# 205-020_001_smps_boost_fromCell.net
KiCad netlist of a schematic drawn in EAGLE
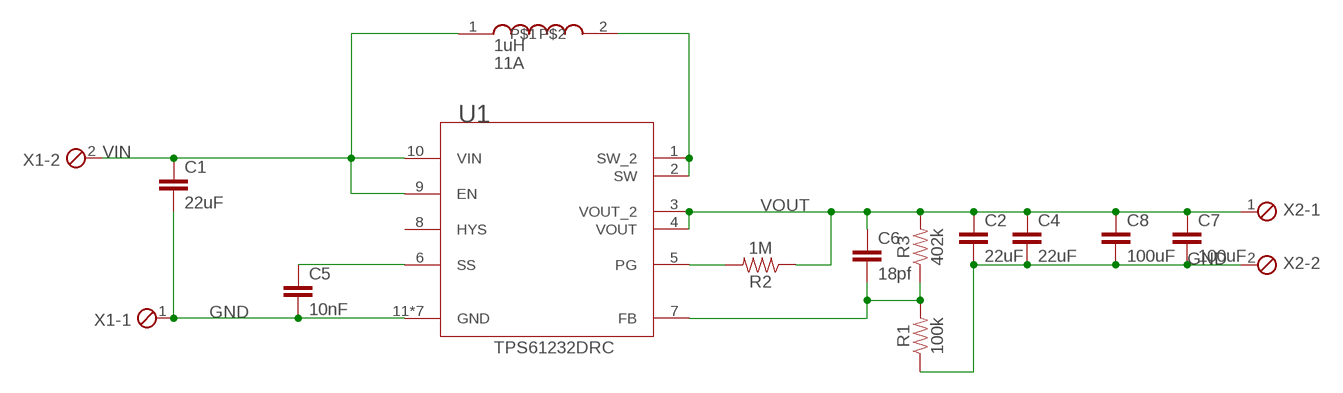
[diagram p0: schematic, sheet 1]

(export (version "E")
  (design (tool "Eeschema 10.0.6"))
  (components
    (comp (ref "C1")
      (value "22uF")
      (footprint "eagle-import:0805")
      (libsource (lib "eagle-import") (part "22UF-0805-16V-20%"))
    )
    (comp (ref "C2")
      (value "22uF")
      (footprint "eagle-import:0805")
      (libsource (lib "eagle-import") (part "22UF-0805-16V-20%"))
    )
    (comp (ref "C4")
      (value "22uF")
      (footprint "eagle-import:0805")
      (libsource (lib "eagle-import") (part "22UF-0805-16V-20%"))
    )
    (comp (ref "C5")
      (value "10nF")
      (footprint "eagle-import:0603")
      (libsource (lib "eagle-import") (part "10NF-0603-50V-10%"))
    )
    (comp (ref "C6")
      (value "18pf")
      (footprint "eagle-import:0805")
      (libsource (lib "eagle-import") (part "CAP-0805"))
    )
    (comp (ref "C7")
      (value "100uF")
      (footprint "eagle-import:1206")
      (libsource (lib "eagle-import") (part "CAP-1206"))
    )
    (comp (ref "C8")
      (value "100uF")
      (footprint "eagle-import:1206")
      (libsource (lib "eagle-import") (part "CAP-1206"))
    )
    (comp (ref "R1")
      (value "100k")
      (footprint "eagle-import:0603")
      (libsource (lib "eagle-import") (part "100KOHM-0603-1/10W-1%"))
    )
    (comp (ref "R2")
      (value "1M")
      (footprint "eagle-import:0603")
      (libsource (lib "eagle-import") (part "1MOHM-0603-1/4W-5%"))
    )
    (comp (ref "R3")
      (value "402k")
      (footprint "eagle-import:0603")
      (libsource (lib "eagle-import") (part "100KOHM-0603-1/10W-1%"))
    )
    (comp (ref "U$1")
      (value "1uH")
      (footprint "eagle-import:07A7")
      (fields (field (name "CURRENT") "11A") (field (name "INDUCTANCE") "1uH"))
      (libsource (lib "eagle-import") (part "LMLP0707"))
    )
    (comp (ref "U1")
      (value "TPS61232DRCR")
      (footprint "eagle-import:DRC0010G")
      (fields
        (field (name "MANUFACTURER") "Texas Instruments")
        (field (name "PARTNUMBER") "TPS61232DRC")
        (field (name "APPROVEDBY") "Not shown in title block")
        (field (name "AUTHOR") "Not shown in title block")
        (field (name "CHECKEDBY") "Not shown in title block")
        (field (name "ENGINEER") "Not shown in title block")
        (field (name "MODIFIEDDATE") "Not shown in title block")
        (field (name "PUBLISHER") "Texas Instruments")
        (field (name "SYMBOLCREATOR") "a0411947")
      )
      (libsource (lib "eagle-import") (part "TPS61232DRCR"))
    )
    (comp (ref "X1")
      (value "MPT2")
      (footprint "eagle-import:2POL254")
      (libsource (lib "eagle-import") (part "MPT2"))
    )
    (comp (ref "X2")
      (value "MPT2")
      (footprint "eagle-import:2POL254")
      (libsource (lib "eagle-import") (part "MPT2"))
    )
  )
  (nets
    (net (code "1") (name "/GND") (class "Default")
      (node (ref "C1") (pin "2") (pinfunction "2_2") (pintype "passive"))
      (node (ref "C2") (pin "2") (pinfunction "2_2") (pintype "passive"))
      (node (ref "C4") (pin "2") (pinfunction "2_2") (pintype "passive"))
      (node (ref "C5") (pin "2") (pinfunction "2_2") (pintype "passive"))
      (node (ref "C7") (pin "2") (pinfunction "2_2") (pintype "passive"))
      (node (ref "C8") (pin "2") (pinfunction "2_2") (pintype "passive"))
      (node (ref "R1") (pin "1") (pinfunction "1_1") (pintype "passive"))
      (node (ref "U1") (pin "11") (pinfunction "GND_11") (pintype "power_in"))
      (node (ref "U1") (pin "11A") (pinfunction "GND_11A") (pintype "power_in"))
      (node (ref "U1") (pin "11B") (pinfunction "GND_11B") (pintype "power_in"))
      (node (ref "U1") (pin "11C") (pinfunction "GND_11C") (pintype "power_in"))
      (node (ref "U1") (pin "11D") (pinfunction "GND_11D") (pintype "power_in"))
      (node (ref "U1") (pin "11E") (pinfunction "GND_11E") (pintype "power_in"))
      (node (ref "U1") (pin "11F") (pinfunction "GND_11F") (pintype "power_in"))
      (node (ref "X1") (pin "1") (pinfunction "1_1") (pintype "passive"))
      (node (ref "X2") (pin "2") (pinfunction "1_2") (pintype "passive"))
    )
    (net (code "2") (name "/VIN") (class "Default")
      (node (ref "C1") (pin "1") (pinfunction "1_1") (pintype "passive"))
      (node (ref "U$1") (pin "1") (pinfunction "P$1_1") (pintype "bidirectional"))
      (node (ref "U1") (pin "10") (pinfunction "VIN_10") (pintype "power_in"))
      (node (ref "U1") (pin "9") (pinfunction "EN_9") (pintype "input"))
      (node (ref "X1") (pin "2") (pinfunction "1_2") (pintype "passive"))
    )
    (net (code "3") (name "/VOUT") (class "Default")
      (node (ref "C2") (pin "1") (pinfunction "1_1") (pintype "passive"))
      (node (ref "C4") (pin "1") (pinfunction "1_1") (pintype "passive"))
      (node (ref "C6") (pin "1") (pinfunction "1_1") (pintype "passive"))
      (node (ref "C7") (pin "1") (pinfunction "1_1") (pintype "passive"))
      (node (ref "C8") (pin "1") (pinfunction "1_1") (pintype "passive"))
      (node (ref "R2") (pin "1") (pinfunction "1_1") (pintype "passive"))
      (node (ref "R3") (pin "2") (pinfunction "2_2") (pintype "passive"))
      (node (ref "U1") (pin "3") (pinfunction "VOUT_2_3") (pintype "power_in"))
      (node (ref "U1") (pin "4") (pinfunction "VOUT_4") (pintype "power_in"))
      (node (ref "X2") (pin "1") (pinfunction "1_1") (pintype "passive"))
    )
    (net (code "4") (name "Net-(U$1-P$2)") (class "Default")
      (node (ref "U$1") (pin "2") (pinfunction "P$2_2") (pintype "bidirectional"))
      (node (ref "U1") (pin "1") (pinfunction "SW_2_1") (pintype "power_in"))
      (node (ref "U1") (pin "2") (pinfunction "SW_2") (pintype "power_in"))
    )
    (net (code "5") (name "Net-(U1-FB)") (class "Default")
      (node (ref "C6") (pin "2") (pinfunction "2_2") (pintype "passive"))
      (node (ref "R1") (pin "2") (pinfunction "2_2") (pintype "passive"))
      (node (ref "R3") (pin "1") (pinfunction "1_1") (pintype "passive"))
      (node (ref "U1") (pin "7") (pinfunction "FB_7") (pintype "input"))
    )
    (net (code "6") (name "Net-(U1-PG)") (class "Default")
      (node (ref "R2") (pin "2") (pinfunction "2_2") (pintype "passive"))
      (node (ref "U1") (pin "5") (pinfunction "PG_5") (pintype "output"))
    )
    (net (code "7") (name "Net-(U1-SS)") (class "Default")
      (node (ref "C5") (pin "1") (pinfunction "1_1") (pintype "passive"))
      (node (ref "U1") (pin "6") (pinfunction "SS_6") (pintype "input"))
    )
    (net (code "8") (name "unconnected-(U1-HYS-Pad8)") (class "Default")
      (node (ref "U1") (pin "8") (pinfunction "HYS_8") (pintype "output"))
    )
  )
)
